# FMC_and_Power.net
KiCad netlist of a schematic drawn in Altium Designer
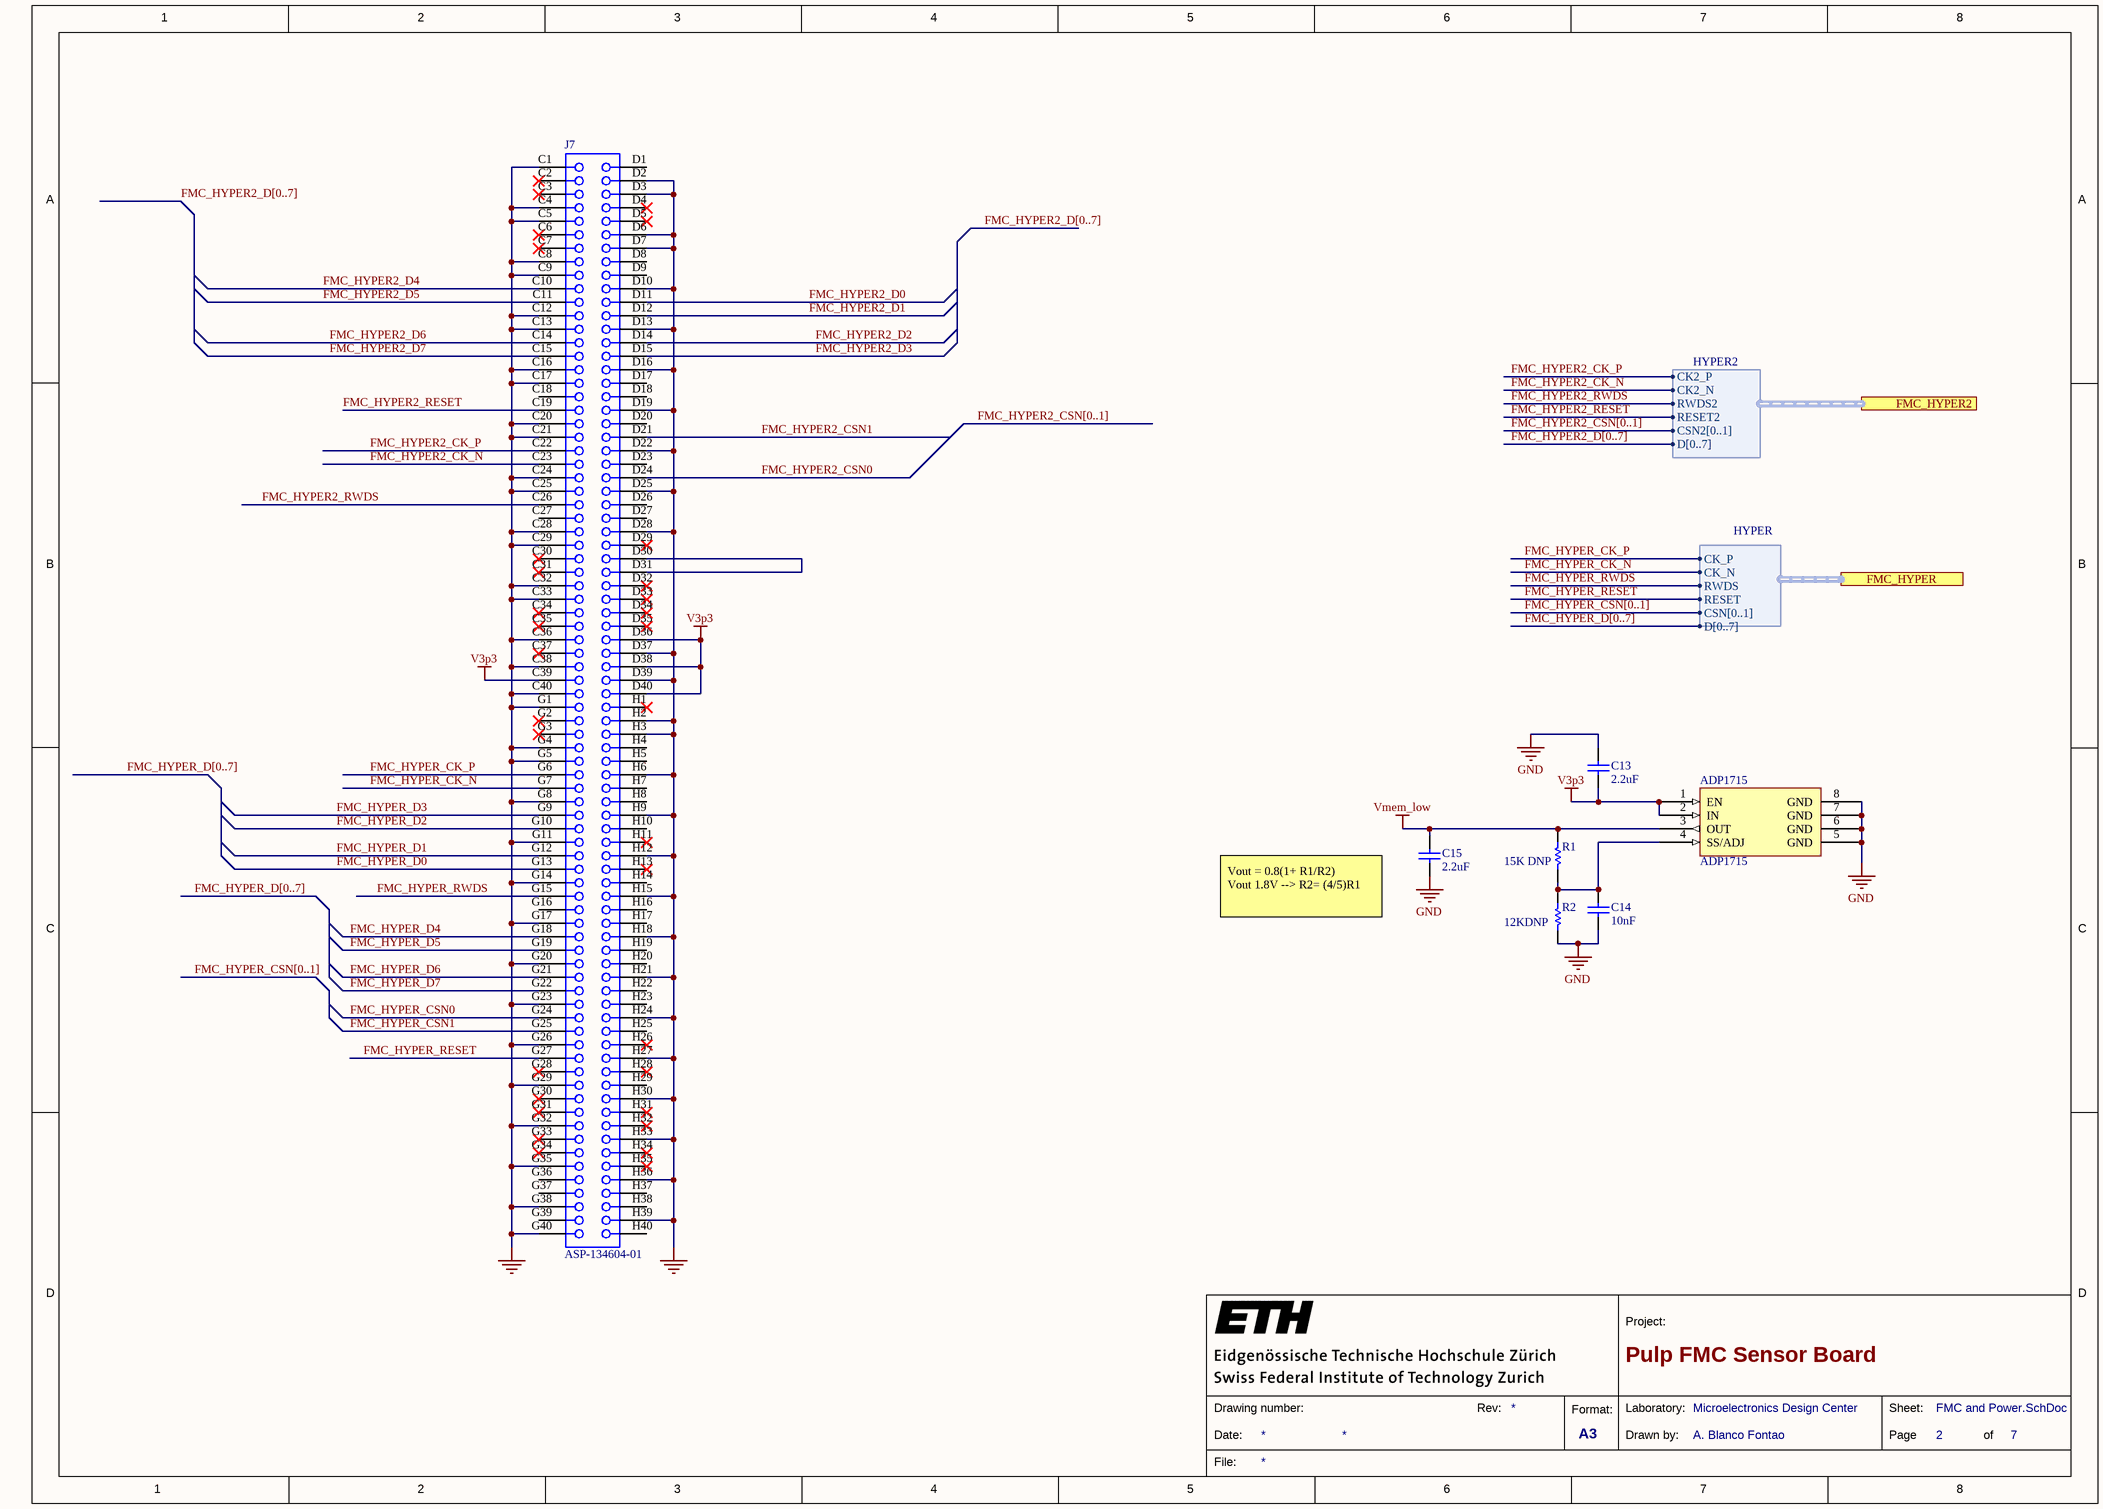
[diagram p0: FMC and Power.SchDoc]

(export (version "E")
  (design (tool "Eeschema 10.0.6"))
  (components
    (comp (ref "ADP1715")
      (value "ADP1715")
      (footprint "TSOP65P490X110-8N")
      (description "IC REG LINEAR 1.8V 500MA 8MSOP")
      (libsource (lib "ADP1715") (part "ADP1715"))
    )
    (comp (ref "C13")
      (value "2.2uF")
      (footprint "CAPC0603(1608)100_N")
      (description "CAP 2.2 µF ±10% 25V X7R 0603 (1608 Metric) Thickness 1.80mm SMD")
      (fields (field (name "TOLERANCE") "Â±10%") (field (name "Comment") "CAP 2.2 µF 25V 0603 (1608)"))
      (libsource (lib "Altium Content Vault") (part "CMP-1035-02588-1"))
    )
    (comp (ref "C14")
      (value "10nF")
      (footprint "CAPC0603(1608)100_N")
      (description "CAP 10nF  ±10% 50V CH  0603 (1608 Metric) Thickness 0.75mm SMD")
      (fields (field (name "TOLERANCE") "Â±10%") (field (name "Comment") "CAP 10nF 50V 0603(1608)"))
      (libsource (lib "Altium Content Vault") (part "CMP-1035-02588-1"))
    )
    (comp (ref "C15")
      (value "2.2uF")
      (footprint "CAPC0603(1608)100_N")
      (description "CAP 2.2 µF ±10% 25V X7R 0603 (1608 Metric) Thickness 1.80mm SMD")
      (fields (field (name "TOLERANCE") "Â±10%") (field (name "Comment") "CAP 2.2 µF 25V 0603 (1608)"))
      (libsource (lib "Altium Content Vault") (part "CMP-1035-02588-1"))
    )
    (comp (ref "J7")
      (value "ASP-134604-01")
      (footprint "ASP-134604-01")
      (description "Conn Array Terminal FMC Male SKT 160 POS 1.27mm Solder ST SMD")
      (fields (field (name "MANUFACTURER") "Samtec"))
      (libsource (lib "ETHZ Vault") (part "ASP-134604-01"))
    )
    (comp (ref "R1")
      (value "15K DNP")
      (footprint "RESC0603(1608)_N")
      (description "15K 0.1W 5% 0603 (1608 Metric)  SMD")
      (fields (field (name "TOLERANCE") "5 %") (field (name "POWER") "0.1 W"))
      (libsource (lib "Altium Content Vault") (part "CMP-1012-00098-1"))
    )
    (comp (ref "R2")
      (value "12KDNP")
      (footprint "RESC0603(1608)_N")
      (description "12K 0.1W 5% 0603 (1608 Metric)  SMD")
      (fields (field (name "TOLERANCE") "5 %") (field (name "POWER") "0.1 W"))
      (libsource (lib "Altium Content Vault") (part "CMP-1012-00098-1"))
    )
  )
  (nets
    (net (code "3") (name "/FMC_HYPER2_CK_N") (class "Default")
      (node (ref "J7") (pin "C23") (pinfunction "C23_C23") (pintype "passive"))
    )
    (net (code "4") (name "/FMC_HYPER2_CK_P") (class "Default")
      (node (ref "J7") (pin "C22") (pinfunction "C22_C22") (pintype "passive"))
    )
    (net (code "5") (name "/FMC_HYPER2_CSN0") (class "Default")
      (node (ref "J7") (pin "D24") (pinfunction "D24_D24") (pintype "passive"))
    )
    (net (code "6") (name "/FMC_HYPER2_CSN1") (class "Default")
      (node (ref "J7") (pin "D21") (pinfunction "D21_D21") (pintype "passive"))
    )
    (net (code "8") (name "/FMC_HYPER2_D0") (class "Default")
      (node (ref "J7") (pin "D11") (pinfunction "D11_D11") (pintype "passive"))
    )
    (net (code "9") (name "/FMC_HYPER2_D1") (class "Default")
      (node (ref "J7") (pin "D12") (pinfunction "D12_D12") (pintype "passive"))
    )
    (net (code "10") (name "/FMC_HYPER2_D2") (class "Default")
      (node (ref "J7") (pin "D14") (pinfunction "D14_D14") (pintype "passive"))
    )
    (net (code "11") (name "/FMC_HYPER2_D3") (class "Default")
      (node (ref "J7") (pin "D15") (pinfunction "D15_D15") (pintype "passive"))
    )
    (net (code "12") (name "/FMC_HYPER2_D4") (class "Default")
      (node (ref "J7") (pin "C10") (pinfunction "C10_C10") (pintype "passive"))
    )
    (net (code "13") (name "/FMC_HYPER2_D5") (class "Default")
      (node (ref "J7") (pin "C11") (pinfunction "C11_C11") (pintype "passive"))
    )
    (net (code "14") (name "/FMC_HYPER2_D6") (class "Default")
      (node (ref "J7") (pin "C14") (pinfunction "C14_C14") (pintype "passive"))
    )
    (net (code "15") (name "/FMC_HYPER2_D7") (class "Default")
      (node (ref "J7") (pin "C15") (pinfunction "C15_C15") (pintype "passive"))
    )
    (net (code "17") (name "/FMC_HYPER2_RESET") (class "Default")
      (node (ref "J7") (pin "C19") (pinfunction "C19_C19") (pintype "passive"))
    )
    (net (code "18") (name "/FMC_HYPER2_RWDS") (class "Default")
      (node (ref "J7") (pin "C26") (pinfunction "C26_C26") (pintype "passive"))
    )
    (net (code "20") (name "/FMC_HYPER_CK_N") (class "Default")
      (node (ref "J7") (pin "G7") (pinfunction "G7_G7") (pintype "passive"))
    )
    (net (code "21") (name "/FMC_HYPER_CK_P") (class "Default")
      (node (ref "J7") (pin "G6") (pinfunction "G6_G6") (pintype "passive"))
    )
    (net (code "22") (name "/FMC_HYPER_CSN0") (class "Default")
      (node (ref "J7") (pin "G24") (pinfunction "G24_G24") (pintype "passive"))
    )
    (net (code "23") (name "/FMC_HYPER_CSN1") (class "Default")
      (node (ref "J7") (pin "G25") (pinfunction "G25_G25") (pintype "passive"))
    )
    (net (code "25") (name "/FMC_HYPER_D0") (class "Default")
      (node (ref "J7") (pin "G13") (pinfunction "G13_G13") (pintype "passive"))
    )
    (net (code "26") (name "/FMC_HYPER_D1") (class "Default")
      (node (ref "J7") (pin "G12") (pinfunction "G12_G12") (pintype "passive"))
    )
    (net (code "27") (name "/FMC_HYPER_D2") (class "Default")
      (node (ref "J7") (pin "G10") (pinfunction "G10_G10") (pintype "passive"))
    )
    (net (code "28") (name "/FMC_HYPER_D3") (class "Default")
      (node (ref "J7") (pin "G9") (pinfunction "G9_G9") (pintype "passive"))
    )
    (net (code "29") (name "/FMC_HYPER_D4") (class "Default")
      (node (ref "J7") (pin "G18") (pinfunction "G18_G18") (pintype "passive"))
    )
    (net (code "30") (name "/FMC_HYPER_D5") (class "Default")
      (node (ref "J7") (pin "G19") (pinfunction "G19_G19") (pintype "passive"))
    )
    (net (code "31") (name "/FMC_HYPER_D6") (class "Default")
      (node (ref "J7") (pin "G21") (pinfunction "G21_G21") (pintype "passive"))
    )
    (net (code "32") (name "/FMC_HYPER_D7") (class "Default")
      (node (ref "J7") (pin "G22") (pinfunction "G22_G22") (pintype "passive"))
    )
    (net (code "34") (name "/FMC_HYPER_RESET") (class "Default")
      (node (ref "J7") (pin "G27") (pinfunction "G27_G27") (pintype "passive"))
    )
    (net (code "35") (name "/FMC_HYPER_RWDS") (class "Default")
      (node (ref "J7") (pin "G15") (pinfunction "G15_G15") (pintype "passive"))
    )
    (net (code "39") (name "GND") (class "Default")
      (node (ref "ADP1715") (pin "5") (pinfunction "GND_5") (pintype "power_in"))
      (node (ref "ADP1715") (pin "6") (pinfunction "GND_6") (pintype "power_in"))
      (node (ref "ADP1715") (pin "7") (pinfunction "GND_7") (pintype "power_in"))
      (node (ref "ADP1715") (pin "8") (pinfunction "GND_8") (pintype "power_in"))
      (node (ref "C13") (pin "2") (pinfunction "2_2") (pintype "passive"))
      (node (ref "C14") (pin "1") (pinfunction "1_1") (pintype "passive"))
      (node (ref "C15") (pin "1") (pinfunction "1_1") (pintype "passive"))
      (node (ref "J7") (pin "C1") (pinfunction "C1_C1") (pintype "passive"))
      (node (ref "J7") (pin "C12") (pinfunction "C12_C12") (pintype "passive"))
      (node (ref "J7") (pin "C13") (pinfunction "C13_C13") (pintype "passive"))
      (node (ref "J7") (pin "C16") (pinfunction "C16_C16") (pintype "passive"))
      (node (ref "J7") (pin "C17") (pinfunction "C17_C17") (pintype "passive"))
      (node (ref "J7") (pin "C20") (pinfunction "C20_C20") (pintype "passive"))
      (node (ref "J7") (pin "C21") (pinfunction "C21_C21") (pintype "passive"))
      (node (ref "J7") (pin "C24") (pinfunction "C24_C24") (pintype "passive"))
      (node (ref "J7") (pin "C25") (pinfunction "C25_C25") (pintype "passive"))
      (node (ref "J7") (pin "C28") (pinfunction "C28_C28") (pintype "passive"))
      (node (ref "J7") (pin "C29") (pinfunction "C29_C29") (pintype "passive"))
      (node (ref "J7") (pin "C32") (pinfunction "C32_C32") (pintype "passive"))
      (node (ref "J7") (pin "C33") (pinfunction "C33_C33") (pintype "passive"))
      (node (ref "J7") (pin "C36") (pinfunction "C36_C36") (pintype "passive"))
      (node (ref "J7") (pin "C38") (pinfunction "C38_C38") (pintype "passive"))
      (node (ref "J7") (pin "C4") (pinfunction "C4_C4") (pintype "passive"))
      (node (ref "J7") (pin "C40") (pinfunction "C40_C40") (pintype "passive"))
      (node (ref "J7") (pin "C5") (pinfunction "C5_C5") (pintype "passive"))
      (node (ref "J7") (pin "C8") (pinfunction "C8_C8") (pintype "passive"))
      (node (ref "J7") (pin "C9") (pinfunction "C9_C9") (pintype "passive"))
      (node (ref "J7") (pin "D10") (pinfunction "D10_D10") (pintype "passive"))
      (node (ref "J7") (pin "D13") (pinfunction "D13_D13") (pintype "passive"))
      (node (ref "J7") (pin "D16") (pinfunction "D16_D16") (pintype "passive"))
      (node (ref "J7") (pin "D19") (pinfunction "D19_D19") (pintype "passive"))
      (node (ref "J7") (pin "D2") (pinfunction "D2_D2") (pintype "passive"))
      (node (ref "J7") (pin "D22") (pinfunction "D22_D22") (pintype "passive"))
      (node (ref "J7") (pin "D25") (pinfunction "D25_D25") (pintype "passive"))
      (node (ref "J7") (pin "D28") (pinfunction "D28_D28") (pintype "passive"))
      (node (ref "J7") (pin "D3") (pinfunction "D3_D3") (pintype "passive"))
      (node (ref "J7") (pin "D37") (pinfunction "D37_D37") (pintype "passive"))
      (node (ref "J7") (pin "D39") (pinfunction "D39_D39") (pintype "passive"))
      (node (ref "J7") (pin "D6") (pinfunction "D6_D6") (pintype "passive"))
      (node (ref "J7") (pin "D7") (pinfunction "D7_D7") (pintype "passive"))
      (node (ref "J7") (pin "G1") (pinfunction "G1_G1") (pintype "passive"))
      (node (ref "J7") (pin "G11") (pinfunction "G11_G11") (pintype "passive"))
      (node (ref "J7") (pin "G14") (pinfunction "G14_G14") (pintype "passive"))
      (node (ref "J7") (pin "G17") (pinfunction "G17_G17") (pintype "passive"))
      (node (ref "J7") (pin "G20") (pinfunction "G20_G20") (pintype "passive"))
      (node (ref "J7") (pin "G23") (pinfunction "G23_G23") (pintype "passive"))
      (node (ref "J7") (pin "G26") (pinfunction "G26_G26") (pintype "passive"))
      (node (ref "J7") (pin "G29") (pinfunction "G29_G29") (pintype "passive"))
      (node (ref "J7") (pin "G32") (pinfunction "G32_G32") (pintype "passive"))
      (node (ref "J7") (pin "G35") (pinfunction "G35_G35") (pintype "passive"))
      (node (ref "J7") (pin "G38") (pinfunction "G38_G38") (pintype "passive"))
      (node (ref "J7") (pin "G4") (pinfunction "G4_G4") (pintype "passive"))
      (node (ref "J7") (pin "G40") (pinfunction "G40_G40") (pintype "passive"))
      (node (ref "J7") (pin "G5") (pinfunction "G5_G5") (pintype "passive"))
      (node (ref "J7") (pin "G8") (pinfunction "G8_G8") (pintype "passive"))
      (node (ref "J7") (pin "H12") (pinfunction "H12_H12") (pintype "passive"))
      (node (ref "J7") (pin "H15") (pinfunction "H15_H15") (pintype "passive"))
      (node (ref "J7") (pin "H18") (pinfunction "H18_H18") (pintype "passive"))
      (node (ref "J7") (pin "H2") (pinfunction "H2_H2") (pintype "passive"))
      (node (ref "J7") (pin "H21") (pinfunction "H21_H21") (pintype "passive"))
      (node (ref "J7") (pin "H24") (pinfunction "H24_H24") (pintype "passive"))
      (node (ref "J7") (pin "H27") (pinfunction "H27_H27") (pintype "passive"))
      (node (ref "J7") (pin "H3") (pinfunction "H3_H3") (pintype "passive"))
      (node (ref "J7") (pin "H30") (pinfunction "H30_H30") (pintype "passive"))
      (node (ref "J7") (pin "H33") (pinfunction "H33_H33") (pintype "passive"))
      (node (ref "J7") (pin "H36") (pinfunction "H36_H36") (pintype "passive"))
      (node (ref "J7") (pin "H39") (pinfunction "H39_H39") (pintype "passive"))
      (node (ref "J7") (pin "H6") (pinfunction "H6_H6") (pintype "passive"))
      (node (ref "J7") (pin "H9") (pinfunction "H9_H9") (pintype "passive"))
      (node (ref "R2") (pin "1") (pinfunction "1_1") (pintype "passive"))
    )
    (net (code "40") (name "Net-(ADP1715-SS{slash}ADJ)") (class "Default")
      (node (ref "ADP1715") (pin "4") (pinfunction "SS/ADJ_4") (pintype "input"))
      (node (ref "C14") (pin "2") (pinfunction "2_2") (pintype "passive"))
      (node (ref "R1") (pin "1") (pinfunction "1_1") (pintype "passive"))
      (node (ref "R2") (pin "2") (pinfunction "2_2") (pintype "passive"))
    )
    (net (code "41") (name "Net-(J7-PadD30)") (class "Default")
      (node (ref "J7") (pin "D30") (pinfunction "D30_D30") (pintype "passive"))
      (node (ref "J7") (pin "D31") (pinfunction "D31_D31") (pintype "passive"))
    )
    (net (code "42") (name "V3p3") (class "Default")
      (node (ref "ADP1715") (pin "1") (pinfunction "EN_1") (pintype "input"))
      (node (ref "ADP1715") (pin "2") (pinfunction "IN_2") (pintype "input"))
      (node (ref "C13") (pin "1") (pinfunction "1_1") (pintype "passive"))
      (node (ref "J7") (pin "C39") (pinfunction "C39_C39") (pintype "passive"))
      (node (ref "J7") (pin "D36") (pinfunction "D36_D36") (pintype "passive"))
      (node (ref "J7") (pin "D38") (pinfunction "D38_D38") (pintype "passive"))
      (node (ref "J7") (pin "D40") (pinfunction "D40_D40") (pintype "passive"))
    )
    (net (code "43") (name "Vmem_low") (class "Default")
      (node (ref "ADP1715") (pin "3") (pinfunction "OUT_3") (pintype "output"))
      (node (ref "C15") (pin "2") (pinfunction "2_2") (pintype "passive"))
      (node (ref "R1") (pin "2") (pinfunction "2_2") (pintype "passive"))
    )
    (net (code "44") (name "unconnected-(J7-PadC2)") (class "Default")
      (node (ref "J7") (pin "C2") (pinfunction "C2_C2") (pintype "passive+no_connect"))
    )
    (net (code "45") (name "unconnected-(J7-PadC3)") (class "Default")
      (node (ref "J7") (pin "C3") (pinfunction "C3_C3") (pintype "passive+no_connect"))
    )
    (net (code "46") (name "unconnected-(J7-PadC6)") (class "Default")
      (node (ref "J7") (pin "C6") (pinfunction "C6_C6") (pintype "passive+no_connect"))
    )
    (net (code "47") (name "unconnected-(J7-PadC7)") (class "Default")
      (node (ref "J7") (pin "C7") (pinfunction "C7_C7") (pintype "passive+no_connect"))
    )
    (net (code "48") (name "unconnected-(J7-PadC18)") (class "Default")
      (node (ref "J7") (pin "C18") (pinfunction "C18_C18") (pintype "passive"))
    )
    (net (code "49") (name "unconnected-(J7-PadC27)") (class "Default")
      (node (ref "J7") (pin "C27") (pinfunction "C27_C27") (pintype "passive"))
    )
    (net (code "50") (name "unconnected-(J7-PadC30)") (class "Default")
      (node (ref "J7") (pin "C30") (pinfunction "C30_C30") (pintype "passive+no_connect"))
    )
    (net (code "51") (name "unconnected-(J7-PadC31)") (class "Default")
      (node (ref "J7") (pin "C31") (pinfunction "C31_C31") (pintype "passive+no_connect"))
    )
    (net (code "52") (name "unconnected-(J7-PadC34)") (class "Default")
      (node (ref "J7") (pin "C34") (pinfunction "C34_C34") (pintype "passive+no_connect"))
    )
    (net (code "53") (name "unconnected-(J7-PadC35)") (class "Default")
      (node (ref "J7") (pin "C35") (pinfunction "C35_C35") (pintype "passive+no_connect"))
    )
    (net (code "54") (name "unconnected-(J7-PadC37)") (class "Default")
      (node (ref "J7") (pin "C37") (pinfunction "C37_C37") (pintype "passive+no_connect"))
    )
    (net (code "55") (name "unconnected-(J7-PadD1)") (class "Default")
      (node (ref "J7") (pin "D1") (pinfunction "D1_D1") (pintype "passive"))
    )
    (net (code "56") (name "unconnected-(J7-PadD4)") (class "Default")
      (node (ref "J7") (pin "D4") (pinfunction "D4_D4") (pintype "passive+no_connect"))
    )
    (net (code "57") (name "unconnected-(J7-PadD5)") (class "Default")
      (node (ref "J7") (pin "D5") (pinfunction "D5_D5") (pintype "passive+no_connect"))
    )
    (net (code "58") (name "unconnected-(J7-PadD8)") (class "Default")
      (node (ref "J7") (pin "D8") (pinfunction "D8_D8") (pintype "passive"))
    )
    (net (code "59") (name "unconnected-(J7-PadD9)") (class "Default")
      (node (ref "J7") (pin "D9") (pinfunction "D9_D9") (pintype "passive"))
    )
    (net (code "60") (name "unconnected-(J7-PadD17)") (class "Default")
      (node (ref "J7") (pin "D17") (pinfunction "D17_D17") (pintype "passive"))
    )
    (net (code "61") (name "unconnected-(J7-PadD18)") (class "Default")
      (node (ref "J7") (pin "D18") (pinfunction "D18_D18") (pintype "passive"))
    )
    (net (code "62") (name "unconnected-(J7-PadD20)") (class "Default")
      (node (ref "J7") (pin "D20") (pinfunction "D20_D20") (pintype "passive"))
    )
    (net (code "63") (name "unconnected-(J7-PadD23)") (class "Default")
      (node (ref "J7") (pin "D23") (pinfunction "D23_D23") (pintype "passive"))
    )
    (net (code "64") (name "unconnected-(J7-PadD26)") (class "Default")
      (node (ref "J7") (pin "D26") (pinfunction "D26_D26") (pintype "passive"))
    )
    (net (code "65") (name "unconnected-(J7-PadD27)") (class "Default")
      (node (ref "J7") (pin "D27") (pinfunction "D27_D27") (pintype "passive"))
    )
    (net (code "66") (name "unconnected-(J7-PadD29)") (class "Default")
      (node (ref "J7") (pin "D29") (pinfunction "D29_D29") (pintype "passive+no_connect"))
    )
    (net (code "67") (name "unconnected-(J7-PadD32)") (class "Default")
      (node (ref "J7") (pin "D32") (pinfunction "D32_D32") (pintype "passive+no_connect"))
    )
    (net (code "68") (name "unconnected-(J7-PadD33)") (class "Default")
      (node (ref "J7") (pin "D33") (pinfunction "D33_D33") (pintype "passive+no_connect"))
    )
    (net (code "69") (name "unconnected-(J7-PadD34)") (class "Default")
      (node (ref "J7") (pin "D34") (pinfunction "D34_D34") (pintype "passive+no_connect"))
    )
    (net (code "70") (name "unconnected-(J7-PadD35)") (class "Default")
      (node (ref "J7") (pin "D35") (pinfunction "D35_D35") (pintype "passive+no_connect"))
    )
    (net (code "71") (name "unconnected-(J7-PadG2)") (class "Default")
      (node (ref "J7") (pin "G2") (pinfunction "G2_G2") (pintype "passive+no_connect"))
    )
    (net (code "72") (name "unconnected-(J7-PadG3)") (class "Default")
      (node (ref "J7") (pin "G3") (pinfunction "G3_G3") (pintype "passive+no_connect"))
    )
    (net (code "73") (name "unconnected-(J7-PadG16)") (class "Default")
      (node (ref "J7") (pin "G16") (pinfunction "G16_G16") (pintype "passive"))
    )
    (net (code "74") (name "unconnected-(J7-PadG28)") (class "Default")
      (node (ref "J7") (pin "G28") (pinfunction "G28_G28") (pintype "passive+no_connect"))
    )
    (net (code "75") (name "unconnected-(J7-PadG30)") (class "Default")
      (node (ref "J7") (pin "G30") (pinfunction "G30_G30") (pintype "passive+no_connect"))
    )
    (net (code "76") (name "unconnected-(J7-PadG31)") (class "Default")
      (node (ref "J7") (pin "G31") (pinfunction "G31_G31") (pintype "passive+no_connect"))
    )
    (net (code "77") (name "unconnected-(J7-PadG33)") (class "Default")
      (node (ref "J7") (pin "G33") (pinfunction "G33_G33") (pintype "passive+no_connect"))
    )
    (net (code "78") (name "unconnected-(J7-PadG34)") (class "Default")
      (node (ref "J7") (pin "G34") (pinfunction "G34_G34") (pintype "passive+no_connect"))
    )
    (net (code "79") (name "unconnected-(J7-PadG36)") (class "Default")
      (node (ref "J7") (pin "G36") (pinfunction "G36_G36") (pintype "passive"))
    )
    (net (code "80") (name "unconnected-(J7-PadG37)") (class "Default")
      (node (ref "J7") (pin "G37") (pinfunction "G37_G37") (pintype "passive"))
    )
    (net (code "81") (name "unconnected-(J7-PadG39)") (class "Default")
      (node (ref "J7") (pin "G39") (pinfunction "G39_G39") (pintype "passive"))
    )
    (net (code "82") (name "unconnected-(J7-PadH1)") (class "Default")
      (node (ref "J7") (pin "H1") (pinfunction "H1_H1") (pintype "passive+no_connect"))
    )
    (net (code "83") (name "unconnected-(J7-PadH4)") (class "Default")
      (node (ref "J7") (pin "H4") (pinfunction "H4_H4") (pintype "passive"))
    )
    (net (code "84") (name "unconnected-(J7-PadH5)") (class "Default")
      (node (ref "J7") (pin "H5") (pinfunction "H5_H5") (pintype "passive"))
    )
    (net (code "85") (name "unconnected-(J7-PadH7)") (class "Default")
      (node (ref "J7") (pin "H7") (pinfunction "H7_H7") (pintype "passive"))
    )
    (net (code "86") (name "unconnected-(J7-PadH8)") (class "Default")
      (node (ref "J7") (pin "H8") (pinfunction "H8_H8") (pintype "passive"))
    )
    (net (code "87") (name "unconnected-(J7-PadH10)") (class "Default")
      (node (ref "J7") (pin "H10") (pinfunction "H10_H10") (pintype "passive"))
    )
    (net (code "88") (name "unconnected-(J7-PadH11)") (class "Default")
      (node (ref "J7") (pin "H11") (pinfunction "H11_H11") (pintype "passive+no_connect"))
    )
    (net (code "89") (name "unconnected-(J7-PadH13)") (class "Default")
      (node (ref "J7") (pin "H13") (pinfunction "H13_H13") (pintype "passive+no_connect"))
    )
    (net (code "90") (name "unconnected-(J7-PadH14)") (class "Default")
      (node (ref "J7") (pin "H14") (pinfunction "H14_H14") (pintype "passive"))
    )
    (net (code "91") (name "unconnected-(J7-PadH16)") (class "Default")
      (node (ref "J7") (pin "H16") (pinfunction "H16_H16") (pintype "passive"))
    )
    (net (code "92") (name "unconnected-(J7-PadH17)") (class "Default")
      (node (ref "J7") (pin "H17") (pinfunction "H17_H17") (pintype "passive"))
    )
    (net (code "93") (name "unconnected-(J7-PadH19)") (class "Default")
      (node (ref "J7") (pin "H19") (pinfunction "H19_H19") (pintype "passive"))
    )
    (net (code "94") (name "unconnected-(J7-PadH20)") (class "Default")
      (node (ref "J7") (pin "H20") (pinfunction "H20_H20") (pintype "passive"))
    )
    (net (code "95") (name "unconnected-(J7-PadH22)") (class "Default")
      (node (ref "J7") (pin "H22") (pinfunction "H22_H22") (pintype "passive"))
    )
    (net (code "96") (name "unconnected-(J7-PadH23)") (class "Default")
      (node (ref "J7") (pin "H23") (pinfunction "H23_H23") (pintype "passive"))
    )
    (net (code "97") (name "unconnected-(J7-PadH25)") (class "Default")
      (node (ref "J7") (pin "H25") (pinfunction "H25_H25") (pintype "passive"))
    )
    (net (code "98") (name "unconnected-(J7-PadH26)") (class "Default")
      (node (ref "J7") (pin "H26") (pinfunction "H26_H26") (pintype "passive+no_connect"))
    )
    (net (code "99") (name "unconnected-(J7-PadH28)") (class "Default")
      (node (ref "J7") (pin "H28") (pinfunction "H28_H28") (pintype "passive+no_connect"))
    )
    (net (code "100") (name "unconnected-(J7-PadH29)") (class "Default")
      (node (ref "J7") (pin "H29") (pinfunction "H29_H29") (pintype "passive"))
    )
    (net (code "101") (name "unconnected-(J7-PadH31)") (class "Default")
      (node (ref "J7") (pin "H31") (pinfunction "H31_H31") (pintype "passive+no_connect"))
    )
    (net (code "102") (name "unconnected-(J7-PadH32)") (class "Default")
      (node (ref "J7") (pin "H32") (pinfunction "H32_H32") (pintype "passive+no_connect"))
    )
    (net (code "103") (name "unconnected-(J7-PadH34)") (class "Default")
      (node (ref "J7") (pin "H34") (pinfunction "H34_H34") (pintype "passive+no_connect"))
    )
    (net (code "104") (name "unconnected-(J7-PadH35)") (class "Default")
      (node (ref "J7") (pin "H35") (pinfunction "H35_H35") (pintype "passive+no_connect"))
    )
    (net (code "105") (name "unconnected-(J7-PadH37)") (class "Default")
      (node (ref "J7") (pin "H37") (pinfunction "H37_H37") (pintype "passive"))
    )
    (net (code "106") (name "unconnected-(J7-PadH38)") (class "Default")
      (node (ref "J7") (pin "H38") (pinfunction "H38_H38") (pintype "passive"))
    )
    (net (code "107") (name "unconnected-(J7-PadH40)") (class "Default")
      (node (ref "J7") (pin "H40") (pinfunction "H40_H40") (pintype "passive"))
    )
  )
)
